# USB-Board.net
KiCad netlist of a schematic drawn in EAGLE
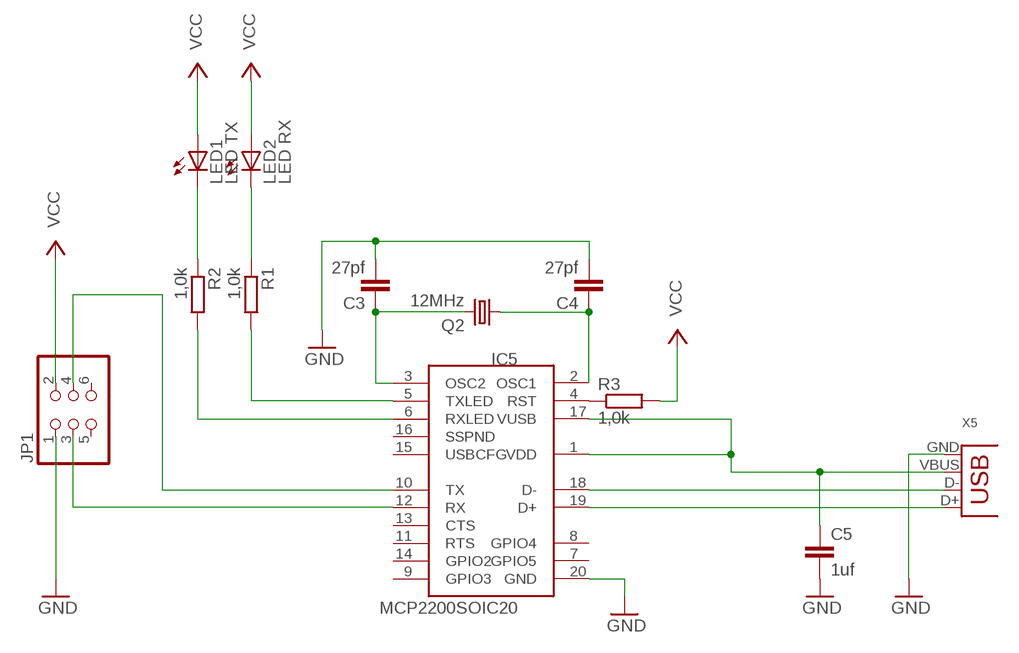
[diagram p0: schematic, sheet 1]

(export (version "E")
  (design (tool "Eeschema 10.0.6"))
  (components
    (comp (ref "C3")
      (value "27pf")
      (footprint "eagle-import:C050-024X044")
      (libsource (lib "eagle-import") (part "C-EU050-024X044"))
    )
    (comp (ref "C4")
      (value "27pf")
      (footprint "eagle-import:C050-024X044")
      (libsource (lib "eagle-import") (part "C-EU050-024X044"))
    )
    (comp (ref "C5")
      (value "1uf")
      (footprint "eagle-import:C5B5.5")
      (libsource (lib "eagle-import") (part "C5/5.5"))
    )
    (comp (ref "IC5")
      (value "MCP2200SOIC20")
      (footprint "eagle-import:SOIC20")
      (libsource (lib "eagle-import") (part "MCP2200SOIC20"))
    )
    (comp (ref "JP1")
      (value "PINHD-2X3")
      (footprint "eagle-import:2X03")
      (libsource (lib "eagle-import") (part "PINHD-2X3"))
    )
    (comp (ref "LED1")
      (value "LED TX")
      (footprint "eagle-import:LED3MM")
      (libsource (lib "eagle-import") (part "LED3MM"))
    )
    (comp (ref "LED2")
      (value "LED RX")
      (footprint "eagle-import:LED3MM")
      (libsource (lib "eagle-import") (part "LED3MM"))
    )
    (comp (ref "Q2")
      (value "12MHz")
      (footprint "eagle-import:HC18U-V")
      (libsource (lib "eagle-import") (part "CRYSTALHC18U-V"))
    )
    (comp (ref "R1")
      (value "1,0k")
      (footprint "eagle-import:0207_10")
      (libsource (lib "eagle-import") (part "R-EU_0207/10"))
    )
    (comp (ref "R2")
      (value "1,0k")
      (footprint "eagle-import:0207_10")
      (libsource (lib "eagle-import") (part "R-EU_0207/10"))
    )
    (comp (ref "R3")
      (value "1,0k")
      (footprint "eagle-import:0207_10")
      (libsource (lib "eagle-import") (part "R-EU_0207/10"))
    )
    (comp (ref "X5")
      (value "USB-B-H")
      (footprint "eagle-import:USB-B-H")
      (libsource (lib "eagle-import") (part "USB-B-H"))
    )
  )
  (nets
    (net (code "1") (name "GND") (class "Default")
      (node (ref "C3") (pin "2") (pinfunction "2_2") (pintype "passive"))
      (node (ref "C4") (pin "2") (pinfunction "2_2") (pintype "passive"))
      (node (ref "C5") (pin "2") (pinfunction "2_2") (pintype "passive"))
      (node (ref "IC5") (pin "20") (pinfunction "GND_20") (pintype "bidirectional"))
      (node (ref "JP1") (pin "1") (pinfunction "1_1") (pintype "passive"))
      (node (ref "X5") (pin "GND") (pinfunction "GND_GND") (pintype "bidirectional"))
    )
    (net (code "2") (name "Net-(IC5-D+)") (class "Default")
      (node (ref "IC5") (pin "19") (pinfunction "D+_19") (pintype "bidirectional"))
      (node (ref "X5") (pin "D+") (pinfunction "D+_D+") (pintype "bidirectional"))
    )
    (net (code "3") (name "Net-(IC5-D-)") (class "Default")
      (node (ref "IC5") (pin "18") (pinfunction "D-_18") (pintype "bidirectional"))
      (node (ref "X5") (pin "D-") (pinfunction "D-_D-") (pintype "bidirectional"))
    )
    (net (code "4") (name "Net-(IC5-OSC1)") (class "Default")
      (node (ref "C4") (pin "1") (pinfunction "1_1") (pintype "passive"))
      (node (ref "IC5") (pin "2") (pinfunction "OSC1_2") (pintype "bidirectional"))
      (node (ref "Q2") (pin "1") (pinfunction "1_1") (pintype "passive"))
    )
    (net (code "5") (name "Net-(IC5-OSC2)") (class "Default")
      (node (ref "C3") (pin "1") (pinfunction "1_1") (pintype "passive"))
      (node (ref "IC5") (pin "3") (pinfunction "OSC2_3") (pintype "bidirectional"))
      (node (ref "Q2") (pin "2") (pinfunction "2_2") (pintype "passive"))
    )
    (net (code "6") (name "Net-(IC5-RST)") (class "Default")
      (node (ref "IC5") (pin "4") (pinfunction "RST_4") (pintype "bidirectional"))
      (node (ref "R3") (pin "1") (pinfunction "1_1") (pintype "passive"))
    )
    (net (code "7") (name "Net-(IC5-RX)") (class "Default")
      (node (ref "IC5") (pin "12") (pinfunction "RX_12") (pintype "bidirectional"))
      (node (ref "JP1") (pin "3") (pinfunction "3_3") (pintype "passive"))
    )
    (net (code "8") (name "Net-(IC5-RXLED)") (class "Default")
      (node (ref "IC5") (pin "6") (pinfunction "RXLED_6") (pintype "bidirectional"))
      (node (ref "R2") (pin "2") (pinfunction "2_2") (pintype "passive"))
    )
    (net (code "9") (name "Net-(IC5-TX)") (class "Default")
      (node (ref "IC5") (pin "10") (pinfunction "TX_10") (pintype "bidirectional"))
      (node (ref "JP1") (pin "4") (pinfunction "4_4") (pintype "passive"))
    )
    (net (code "10") (name "Net-(IC5-TXLED)") (class "Default")
      (node (ref "IC5") (pin "5") (pinfunction "TXLED_5") (pintype "bidirectional"))
      (node (ref "R1") (pin "2") (pinfunction "2_2") (pintype "passive"))
    )
    (net (code "11") (name "Net-(IC5-VDD)") (class "Default")
      (node (ref "C5") (pin "1") (pinfunction "1_1") (pintype "passive"))
      (node (ref "IC5") (pin "1") (pinfunction "VDD_1") (pintype "bidirectional"))
      (node (ref "IC5") (pin "17") (pinfunction "VUSB_17") (pintype "bidirectional"))
      (node (ref "X5") (pin "VBUS") (pinfunction "VBUS_VBUS") (pintype "bidirectional"))
    )
    (net (code "12") (name "Net-(LED1-C)") (class "Default")
      (node (ref "LED1") (pin "K") (pinfunction "C_K") (pintype "passive"))
      (node (ref "R2") (pin "1") (pinfunction "1_1") (pintype "passive"))
    )
    (net (code "13") (name "Net-(LED2-C)") (class "Default")
      (node (ref "LED2") (pin "K") (pinfunction "C_K") (pintype "passive"))
      (node (ref "R1") (pin "1") (pinfunction "1_1") (pintype "passive"))
    )
    (net (code "14") (name "VCC") (class "Default")
      (node (ref "JP1") (pin "2") (pinfunction "2_2") (pintype "passive"))
      (node (ref "LED1") (pin "A") (pinfunction "A_A") (pintype "passive"))
      (node (ref "LED2") (pin "A") (pinfunction "A_A") (pintype "passive"))
      (node (ref "R3") (pin "2") (pinfunction "2_2") (pintype "passive"))
    )
    (net (code "15") (name "unconnected-(IC5-CTS-Pad13)") (class "Default")
      (node (ref "IC5") (pin "13") (pinfunction "CTS_13") (pintype "bidirectional"))
    )
    (net (code "16") (name "unconnected-(IC5-GPIO2-Pad14)") (class "Default")
      (node (ref "IC5") (pin "14") (pinfunction "GPIO2_14") (pintype "bidirectional"))
    )
    (net (code "17") (name "unconnected-(IC5-GPIO3-Pad9)") (class "Default")
      (node (ref "IC5") (pin "9") (pinfunction "GPIO3_9") (pintype "bidirectional"))
    )
    (net (code "18") (name "unconnected-(IC5-GPIO4-Pad8)") (class "Default")
      (node (ref "IC5") (pin "8") (pinfunction "GPIO4_8") (pintype "bidirectional"))
    )
    (net (code "19") (name "unconnected-(IC5-GPIO5-Pad7)") (class "Default")
      (node (ref "IC5") (pin "7") (pinfunction "GPIO5_7") (pintype "bidirectional"))
    )
    (net (code "20") (name "unconnected-(IC5-RTS-Pad11)") (class "Default")
      (node (ref "IC5") (pin "11") (pinfunction "RTS_11") (pintype "bidirectional"))
    )
    (net (code "21") (name "unconnected-(IC5-SSPND-Pad16)") (class "Default")
      (node (ref "IC5") (pin "16") (pinfunction "SSPND_16") (pintype "bidirectional"))
    )
    (net (code "22") (name "unconnected-(IC5-USBCFG-Pad15)") (class "Default")
      (node (ref "IC5") (pin "15") (pinfunction "USBCFG_15") (pintype "bidirectional"))
    )
    (net (code "23") (name "unconnected-(JP1-Pad5)") (class "Default")
      (node (ref "JP1") (pin "5") (pinfunction "5_5") (pintype "passive"))
    )
    (net (code "24") (name "unconnected-(JP1-Pad6)") (class "Default")
      (node (ref "JP1") (pin "6") (pinfunction "6_6") (pintype "passive"))
    )
  )
)
